# MSP430F149.net
KiCad netlist of a schematic drawn in Altium Designer
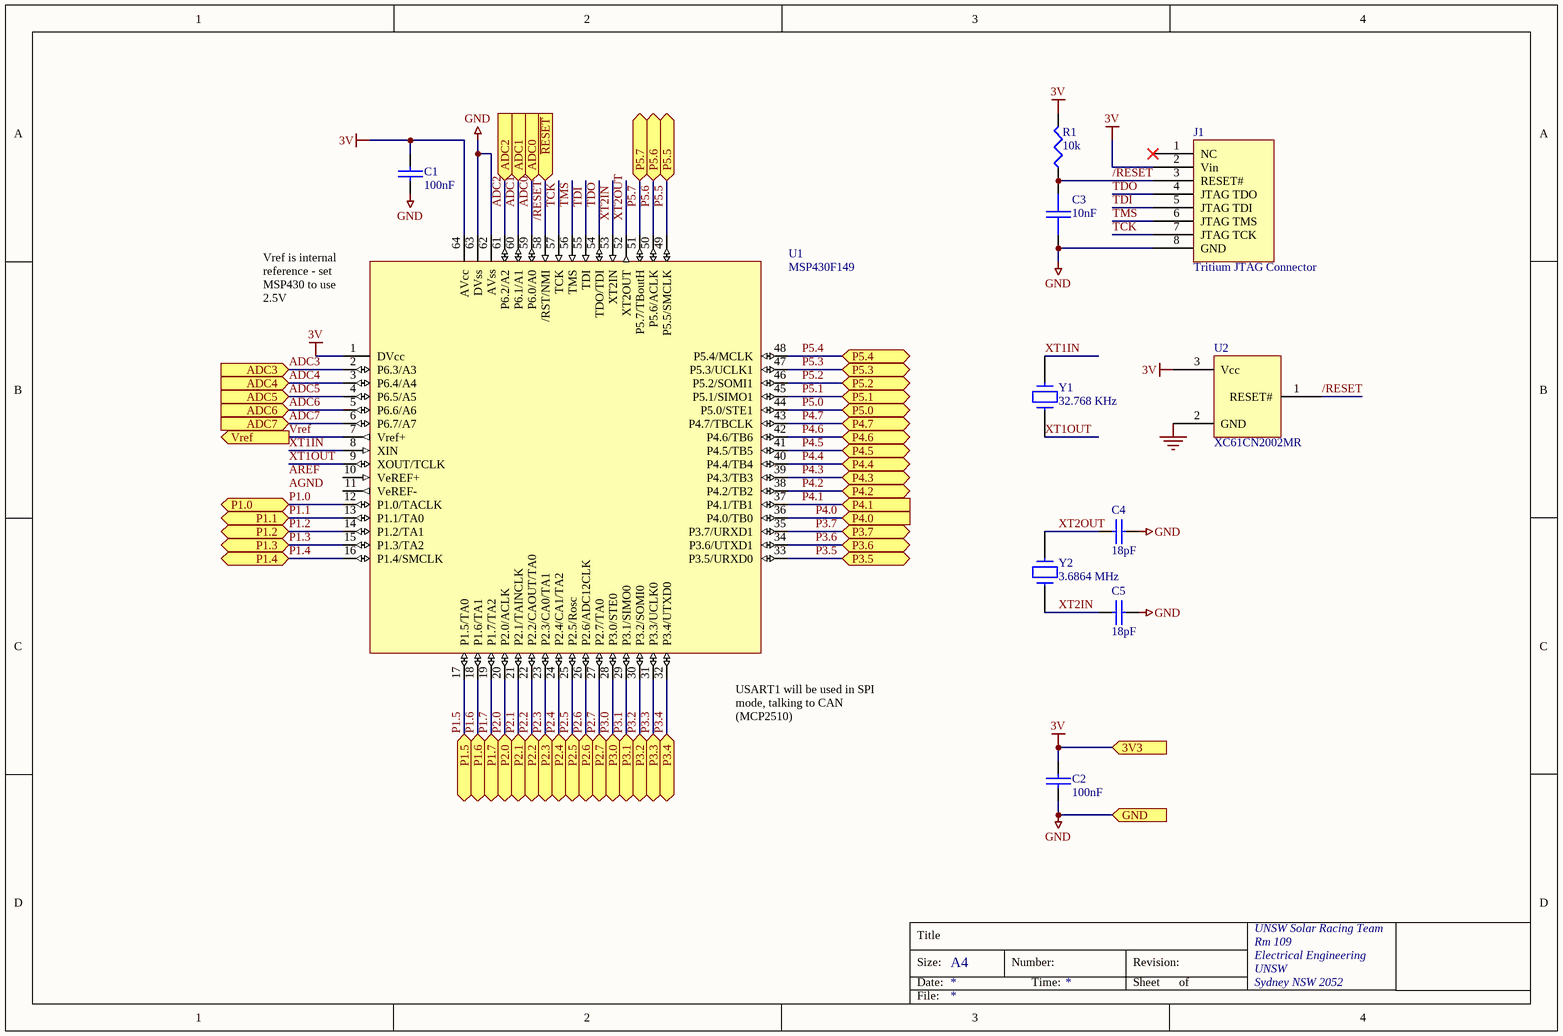
[diagram p0: MSP430F149.SCHDOC]

(export (version "E")
  (design (tool "Eeschema 10.0.6"))
  (components
    (comp (ref "C1")
      (value "100nF")
      (footprint "1608[0603]")
      (description "Capacitor")
      (libsource (lib "*") (part "CAP"))
    )
    (comp (ref "C2")
      (value "100nF")
      (footprint "1608[0603]")
      (description "Capacitor")
      (libsource (lib "*") (part "CAP"))
    )
    (comp (ref "C3")
      (value "10nF")
      (footprint "1608[0603]")
      (description "Capacitor")
      (libsource (lib "SunswiftLib20030312RR") (part "CAP"))
    )
    (comp (ref "C4")
      (value "18pF")
      (footprint "1608[0603]")
      (description "Capacitor")
      (libsource (lib "*") (part "CAP"))
    )
    (comp (ref "C5")
      (value "18pF")
      (footprint "1608[0603]")
      (description "Capacitor")
      (libsource (lib "*") (part "CAP"))
    )
    (comp (ref "J1")
      (value "Tritium JTAG Connector")
      (footprint "Connectors:IDC8")
      (description "Tritium JTAG interface for MSP430")
      (libsource (lib "SunswiftLib20030312RR") (part "430F_JTAG_TRITIUM"))
    )
    (comp (ref "R1")
      (value "10k")
      (footprint "1608[0603]")
      (description "Resistor")
      (libsource (lib "SunswiftLib20030312RR") (part "RES1"))
    )
    (comp (ref "U1")
      (value "MSP430F149")
      (footprint "Footprint:QFP64")
      (libsource (lib "SunswiftLib20030312RR") (part "MSP430F14X"))
    )
    (comp (ref "U2")
      (value "XC61CN2002MR")
      (footprint "IPC-SM-782 Section 8.6 SOT23:SOT23")
      (description "SOT23 reset generator")
      (libsource (lib "*") (part "XC61F"))
    )
    (comp (ref "Y1")
      (value "32.768 KHz")
      (footprint "WATCHA")
      (description "Crystal")
      (libsource (lib "*") (part "CRYSTAL"))
    )
    (comp (ref "Y2")
      (value "3.6864 MHz")
      (footprint "HC49/4H")
      (description "Crystal")
      (libsource (lib "*") (part "CRYSTAL"))
    )
  )
  (nets
    (net (code "1") (name "/ADC0") (class "Default")
      (node (ref "U1") (pin "59") (pinfunction "P6.0/A0_59") (pintype "bidirectional"))
    )
    (net (code "2") (name "/ADC1") (class "Default")
      (node (ref "U1") (pin "60") (pinfunction "P6.1/A1_60") (pintype "bidirectional"))
    )
    (net (code "3") (name "/ADC2") (class "Default")
      (node (ref "U1") (pin "61") (pinfunction "P6.2/A2_61") (pintype "bidirectional"))
    )
    (net (code "4") (name "/ADC3") (class "Default")
      (node (ref "U1") (pin "2") (pinfunction "P6.3/A3_2") (pintype "bidirectional"))
    )
    (net (code "5") (name "/ADC4") (class "Default")
      (node (ref "U1") (pin "3") (pinfunction "P6.4/A4_3") (pintype "bidirectional"))
    )
    (net (code "6") (name "/ADC5") (class "Default")
      (node (ref "U1") (pin "4") (pinfunction "P6.5/A5_4") (pintype "bidirectional"))
    )
    (net (code "7") (name "/ADC6") (class "Default")
      (node (ref "U1") (pin "5") (pinfunction "P6.6/A6_5") (pintype "bidirectional"))
    )
    (net (code "8") (name "/ADC7") (class "Default")
      (node (ref "U1") (pin "6") (pinfunction "P6.7/A7_6") (pintype "bidirectional"))
    )
    (net (code "11") (name "/P1.0") (class "Default")
      (node (ref "U1") (pin "12") (pinfunction "P1.0/TACLK_12") (pintype "bidirectional"))
    )
    (net (code "12") (name "/P1.1") (class "Default")
      (node (ref "U1") (pin "13") (pinfunction "P1.1/TA0_13") (pintype "bidirectional"))
    )
    (net (code "13") (name "/P1.2") (class "Default")
      (node (ref "U1") (pin "14") (pinfunction "P1.2/TA1_14") (pintype "bidirectional"))
    )
    (net (code "14") (name "/P1.3") (class "Default")
      (node (ref "U1") (pin "15") (pinfunction "P1.3/TA2_15") (pintype "bidirectional"))
    )
    (net (code "15") (name "/P1.4") (class "Default")
      (node (ref "U1") (pin "16") (pinfunction "P1.4/SMCLK_16") (pintype "bidirectional"))
    )
    (net (code "16") (name "/P1.5") (class "Default")
      (node (ref "U1") (pin "17") (pinfunction "P1.5/TA0_17") (pintype "bidirectional"))
    )
    (net (code "17") (name "/P1.6") (class "Default")
      (node (ref "U1") (pin "18") (pinfunction "P1.6/TA1_18") (pintype "bidirectional"))
    )
    (net (code "18") (name "/P1.7") (class "Default")
      (node (ref "U1") (pin "19") (pinfunction "P1.7/TA2_19") (pintype "bidirectional"))
    )
    (net (code "19") (name "/P2.0") (class "Default")
      (node (ref "U1") (pin "20") (pinfunction "P2.0/ACLK_20") (pintype "bidirectional"))
    )
    (net (code "20") (name "/P2.1") (class "Default")
      (node (ref "U1") (pin "21") (pinfunction "P2.1/TAINCLK_21") (pintype "bidirectional"))
    )
    (net (code "21") (name "/P2.2") (class "Default")
      (node (ref "U1") (pin "22") (pinfunction "P2.2/CAOUT/TA0_22") (pintype "bidirectional"))
    )
    (net (code "22") (name "/P2.3") (class "Default")
      (node (ref "U1") (pin "23") (pinfunction "P2.3/CA0/TA1_23") (pintype "bidirectional"))
    )
    (net (code "23") (name "/P2.4") (class "Default")
      (node (ref "U1") (pin "24") (pinfunction "P2.4/CA1/TA2_24") (pintype "bidirectional"))
    )
    (net (code "24") (name "/P2.5") (class "Default")
      (node (ref "U1") (pin "25") (pinfunction "P2.5/Rosc_25") (pintype "bidirectional"))
    )
    (net (code "25") (name "/P2.6") (class "Default")
      (node (ref "U1") (pin "26") (pinfunction "P2.6/ADC12CLK_26") (pintype "bidirectional"))
    )
    (net (code "26") (name "/P2.7") (class "Default")
      (node (ref "U1") (pin "27") (pinfunction "P2.7/TA0_27") (pintype "bidirectional"))
    )
    (net (code "27") (name "/P3.0") (class "Default")
      (node (ref "U1") (pin "28") (pinfunction "P3.0/STE0_28") (pintype "bidirectional"))
    )
    (net (code "28") (name "/P3.1") (class "Default")
      (node (ref "U1") (pin "29") (pinfunction "P3.1/SIMO0_29") (pintype "bidirectional"))
    )
    (net (code "29") (name "/P3.2") (class "Default")
      (node (ref "U1") (pin "30") (pinfunction "P3.2/SOMI0_30") (pintype "bidirectional"))
    )
    (net (code "30") (name "/P3.3") (class "Default")
      (node (ref "U1") (pin "31") (pinfunction "P3.3/UCLK0_31") (pintype "bidirectional"))
    )
    (net (code "31") (name "/P3.4") (class "Default")
      (node (ref "U1") (pin "32") (pinfunction "P3.4/UTXD0_32") (pintype "bidirectional"))
    )
    (net (code "32") (name "/P3.5") (class "Default")
      (node (ref "U1") (pin "33") (pinfunction "P3.5/URXD0_33") (pintype "bidirectional"))
    )
    (net (code "33") (name "/P3.6") (class "Default")
      (node (ref "U1") (pin "34") (pinfunction "P3.6/UTXD1_34") (pintype "bidirectional"))
    )
    (net (code "34") (name "/P3.7") (class "Default")
      (node (ref "U1") (pin "35") (pinfunction "P3.7/URXD1_35") (pintype "bidirectional"))
    )
    (net (code "35") (name "/P4.0") (class "Default")
      (node (ref "U1") (pin "36") (pinfunction "P4.0/TB0_36") (pintype "bidirectional"))
    )
    (net (code "36") (name "/P4.1") (class "Default")
      (node (ref "U1") (pin "37") (pinfunction "P4.1/TB1_37") (pintype "bidirectional"))
    )
    (net (code "37") (name "/P4.2") (class "Default")
      (node (ref "U1") (pin "38") (pinfunction "P4.2/TB2_38") (pintype "bidirectional"))
    )
    (net (code "38") (name "/P4.3") (class "Default")
      (node (ref "U1") (pin "39") (pinfunction "P4.3/TB3_39") (pintype "bidirectional"))
    )
    (net (code "39") (name "/P4.4") (class "Default")
      (node (ref "U1") (pin "40") (pinfunction "P4.4/TB4_40") (pintype "bidirectional"))
    )
    (net (code "40") (name "/P4.5") (class "Default")
      (node (ref "U1") (pin "41") (pinfunction "P4.5/TB5_41") (pintype "bidirectional"))
    )
    (net (code "41") (name "/P4.6") (class "Default")
      (node (ref "U1") (pin "42") (pinfunction "P4.6/TB6_42") (pintype "bidirectional"))
    )
    (net (code "42") (name "/P4.7") (class "Default")
      (node (ref "U1") (pin "43") (pinfunction "P4.7/TBCLK_43") (pintype "bidirectional"))
    )
    (net (code "43") (name "/P5.0") (class "Default")
      (node (ref "U1") (pin "44") (pinfunction "P5.0/STE1_44") (pintype "bidirectional"))
    )
    (net (code "44") (name "/P5.1") (class "Default")
      (node (ref "U1") (pin "45") (pinfunction "P5.1/SIMO1_45") (pintype "bidirectional"))
    )
    (net (code "45") (name "/P5.2") (class "Default")
      (node (ref "U1") (pin "46") (pinfunction "P5.2/SOMI1_46") (pintype "bidirectional"))
    )
    (net (code "46") (name "/P5.3") (class "Default")
      (node (ref "U1") (pin "47") (pinfunction "P5.3/UCLK1_47") (pintype "bidirectional"))
    )
    (net (code "47") (name "/P5.4") (class "Default")
      (node (ref "U1") (pin "48") (pinfunction "P5.4/MCLK_48") (pintype "bidirectional"))
    )
    (net (code "48") (name "/P5.5") (class "Default")
      (node (ref "U1") (pin "49") (pinfunction "P5.5/SMCLK_49") (pintype "bidirectional"))
    )
    (net (code "49") (name "/P5.6") (class "Default")
      (node (ref "U1") (pin "50") (pinfunction "P5.6/ACLK_50") (pintype "bidirectional"))
    )
    (net (code "50") (name "/P5.7") (class "Default")
      (node (ref "U1") (pin "51") (pinfunction "P5.7/TBoutH_51") (pintype "bidirectional"))
    )
    (net (code "51") (name "/TCK") (class "Default")
      (node (ref "J1") (pin "7") (pinfunction "JTAG_TCK_7") (pintype "passive"))
      (node (ref "U1") (pin "57") (pinfunction "TCK_57") (pintype "input"))
    )
    (net (code "52") (name "/TDI") (class "Default")
      (node (ref "J1") (pin "5") (pinfunction "JTAG_TDI_5") (pintype "passive"))
      (node (ref "U1") (pin "55") (pinfunction "TDI_55") (pintype "input"))
    )
    (net (code "53") (name "/TDO") (class "Default")
      (node (ref "J1") (pin "4") (pinfunction "JTAG_TDO_4") (pintype "passive"))
      (node (ref "U1") (pin "54") (pinfunction "TDO/TDI_54") (pintype "bidirectional"))
    )
    (net (code "54") (name "/TMS") (class "Default")
      (node (ref "J1") (pin "6") (pinfunction "JTAG_TMS_6") (pintype "passive"))
      (node (ref "U1") (pin "56") (pinfunction "TMS_56") (pintype "input"))
    )
    (net (code "55") (name "/Vref") (class "Default")
      (node (ref "U1") (pin "7") (pinfunction "Vref+_7") (pintype "output"))
    )
    (net (code "56") (name "/XT1IN") (class "Default")
      (node (ref "U1") (pin "8") (pinfunction "XIN_8") (pintype "input"))
      (node (ref "Y1") (pin "2") (pinfunction "2_2") (pintype "passive"))
    )
    (net (code "57") (name "/XT1OUT") (class "Default")
      (node (ref "U1") (pin "9") (pinfunction "XOUT/TCLK_9") (pintype "bidirectional"))
      (node (ref "Y1") (pin "1") (pinfunction "1_1") (pintype "passive"))
    )
    (net (code "58") (name "/XT2IN") (class "Default")
      (node (ref "C5") (pin "1") (pinfunction "1_1") (pintype "passive"))
      (node (ref "U1") (pin "53") (pinfunction "XT2IN_53") (pintype "input"))
      (node (ref "Y2") (pin "1") (pinfunction "1_1") (pintype "passive"))
    )
    (net (code "59") (name "/XT2OUT") (class "Default")
      (node (ref "C4") (pin "1") (pinfunction "1_1") (pintype "passive"))
      (node (ref "U1") (pin "52") (pinfunction "XT2OUT_52") (pintype "output"))
      (node (ref "Y2") (pin "2") (pinfunction "2_2") (pintype "passive"))
    )
    (net (code "60") (name "/{slash}RESET") (class "Default")
      (node (ref "C3") (pin "1") (pinfunction "1_1") (pintype "passive"))
      (node (ref "J1") (pin "3") (pinfunction "RESET#_3") (pintype "passive"))
      (node (ref "R1") (pin "1") (pinfunction "1_1") (pintype "passive"))
      (node (ref "U1") (pin "58") (pinfunction "/RST/NMI_58") (pintype "input"))
      (node (ref "U2") (pin "1") (pinfunction "RESET#_1") (pintype "passive"))
    )
    (net (code "61") (name "3V") (class "Default")
      (node (ref "C1") (pin "1") (pinfunction "1_1") (pintype "passive"))
      (node (ref "C2") (pin "1") (pinfunction "1_1") (pintype "passive"))
      (node (ref "J1") (pin "2") (pinfunction "Vin_2") (pintype "passive"))
      (node (ref "R1") (pin "2") (pinfunction "2_2") (pintype "passive"))
      (node (ref "U1") (pin "1") (pinfunction "DVcc_1") (pintype "power_in"))
      (node (ref "U1") (pin "64") (pinfunction "AVcc_64") (pintype "power_in"))
      (node (ref "U2") (pin "3") (pinfunction "Vcc_3") (pintype "passive"))
    )
    (net (code "62") (name "GND") (class "Default")
      (node (ref "C1") (pin "2") (pinfunction "2_2") (pintype "passive"))
      (node (ref "C2") (pin "2") (pinfunction "2_2") (pintype "passive"))
      (node (ref "C3") (pin "2") (pinfunction "2_2") (pintype "passive"))
      (node (ref "C4") (pin "2") (pinfunction "2_2") (pintype "passive"))
      (node (ref "C5") (pin "2") (pinfunction "2_2") (pintype "passive"))
      (node (ref "J1") (pin "8") (pinfunction "GND_8") (pintype "passive"))
      (node (ref "U1") (pin "62") (pinfunction "AVss_62") (pintype "power_in"))
      (node (ref "U1") (pin "63") (pinfunction "DVss_63") (pintype "power_in"))
      (node (ref "U2") (pin "2") (pinfunction "GND_2") (pintype "passive"))
    )
    (net (code "63") (name "unconnected-(J1-NC-Pad1)") (class "Default")
      (node (ref "J1") (pin "1") (pinfunction "NC_1") (pintype "passive+no_connect"))
    )
    (net (code "64") (name "unconnected-(U1-VeREF+-Pad10)") (class "Default")
      (node (ref "U1") (pin "10") (pinfunction "VeREF+_10") (pintype "input"))
    )
    (net (code "65") (name "unconnected-(U1-VeREF--Pad11)") (class "Default")
      (node (ref "U1") (pin "11") (pinfunction "VeREF-_11") (pintype "output"))
    )
  )
)
